# Oscar_MainBoard_LCD.net
KiCad netlist of a schematic drawn in Altium Designer
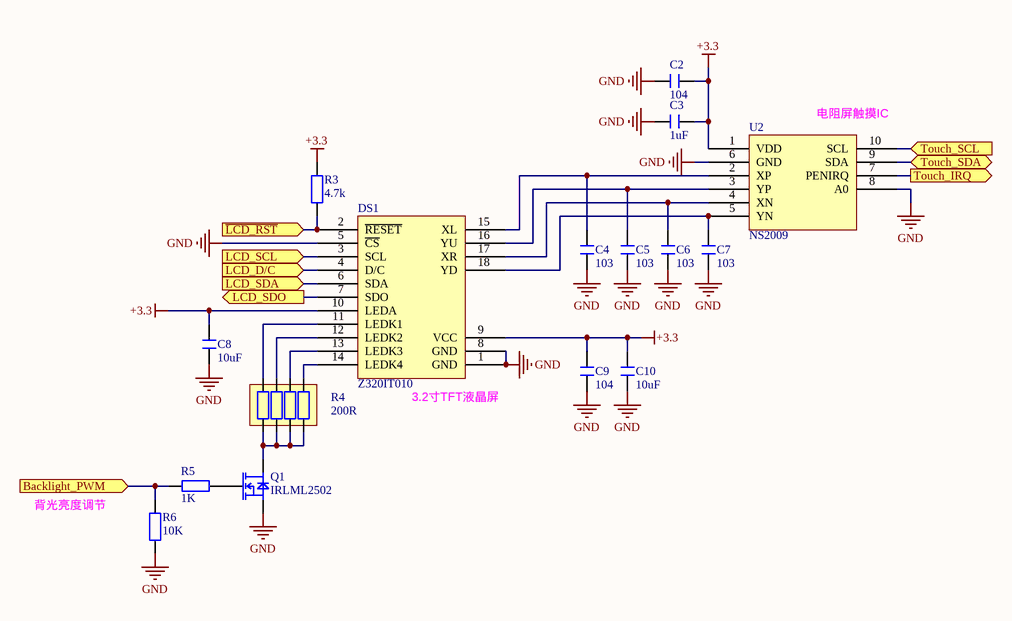
[diagram p0: Oscar_MainBoard_LCD.SchDoc]

(export (version "E")
  (design (tool "Eeschema 10.0.6"))
  (components
    (comp (ref "C2")
      (value "104")
      (footprint "C 0402_L")
      (description "贴片电容")
      (libsource (lib "0.1 - 电阻-电容-电感") (part "C"))
    )
    (comp (ref "C3")
      (value "1uF")
      (footprint "C 0402_L")
      (description "贴片电容")
      (libsource (lib "0.1 - 电阻-电容-电感") (part "C"))
    )
    (comp (ref "C4")
      (value "103")
      (footprint "C 0402_L")
      (description "贴片电容")
      (libsource (lib "0.1 - 电阻-电容-电感") (part "C"))
    )
    (comp (ref "C5")
      (value "103")
      (footprint "C 0402_L")
      (description "贴片电容")
      (libsource (lib "0.1 - 电阻-电容-电感") (part "C"))
    )
    (comp (ref "C6")
      (value "103")
      (footprint "C 0402_L")
      (description "贴片电容")
      (libsource (lib "0.1 - 电阻-电容-电感") (part "C"))
    )
    (comp (ref "C7")
      (value "103")
      (footprint "C 0402_L")
      (description "贴片电容")
      (libsource (lib "0.1 - 电阻-电容-电感") (part "C"))
    )
    (comp (ref "C8")
      (value "10uF")
      (footprint "C 0603_L")
      (description "贴片电容")
      (libsource (lib "0.1 - 电阻-电容-电感") (part "C"))
    )
    (comp (ref "C9")
      (value "104")
      (footprint "C 0402_L")
      (description "贴片电容")
      (libsource (lib "0.1 - 电阻-电容-电感") (part "C"))
    )
    (comp (ref "C10")
      (value "10uF")
      (footprint "C 0603_L")
      (description "贴片电容")
      (libsource (lib "0.1 - 电阻-电容-电感") (part "C"))
    )
    (comp (ref "DS1")
      (value "Z320IT010")
      (footprint "Z320IT010")
      (description "3.2 inch TFT_LCD SPI")
      (libsource (lib "显示器件") (part "Z320IT010"))
    )
    (comp (ref "Q1")
      (value "IRLML2502")
      (footprint "SOT23-3n")
      (description "MOSFET N沟道 20V/4.2A")
      (libsource (lib "0.4 - 三极管-场效应管-可控硅") (part "IRLML2502"))
    )
    (comp (ref "R3")
      (value "4.7k")
      (footprint "R 0402_L")
      (description "贴片电阻")
      (libsource (lib "0.1 - 电阻-电容-电感") (part "R"))
    )
    (comp (ref "R4")
      (value "200R")
      (footprint "RCA-8P4R-0402")
      (description "贴片排阻")
      (libsource (lib "0.1 - 电阻-电容-电感") (part "R-8P4R"))
    )
    (comp (ref "R5")
      (value "1K")
      (footprint "R 0402_L")
      (description "贴片电阻")
      (libsource (lib "0.1 - 电阻-电容-电感") (part "R"))
    )
    (comp (ref "R6")
      (value "10K")
      (footprint "R 0402_L")
      (description "贴片电阻")
      (libsource (lib "0.1 - 电阻-电容-电感") (part "R"))
    )
    (comp (ref "U2")
      (value "NS2009")
      (footprint "MSOP10_N")
      (description "I2C接口的4线制电阻式触摸屏控制电路")
      (libsource (lib "显示器件") (part "NS2009"))
    )
  )
  (nets
    (net (code "1") (name "+3.3") (class "Default")
      (node (ref "C10") (pin "1") (pinfunction "1_1") (pintype "passive"))
      (node (ref "C2") (pin "1") (pinfunction "1_1") (pintype "passive"))
      (node (ref "C3") (pin "1") (pinfunction "1_1") (pintype "passive"))
      (node (ref "C8") (pin "1") (pinfunction "1_1") (pintype "passive"))
      (node (ref "C9") (pin "1") (pinfunction "1_1") (pintype "passive"))
      (node (ref "DS1") (pin "10") (pinfunction "LEDA_10") (pintype "passive"))
      (node (ref "DS1") (pin "9") (pinfunction "VCC_9") (pintype "passive"))
      (node (ref "R3") (pin "2") (pinfunction "2_2") (pintype "passive"))
      (node (ref "U2") (pin "1") (pinfunction "VDD_1") (pintype "passive"))
    )
    (net (code "2") (name "/Backlight_PWM") (class "Default")
      (node (ref "R5") (pin "1") (pinfunction "1_1") (pintype "passive"))
      (node (ref "R6") (pin "2") (pinfunction "2_2") (pintype "passive"))
    )
    (net (code "3") (name "/LCD_D{slash}C") (class "Default")
      (node (ref "DS1") (pin "4") (pinfunction "D/C_4") (pintype "passive"))
    )
    (net (code "4") (name "/LCD_SCL") (class "Default")
      (node (ref "DS1") (pin "3") (pinfunction "SCL_3") (pintype "passive"))
    )
    (net (code "5") (name "/LCD_SDA") (class "Default")
      (node (ref "DS1") (pin "6") (pinfunction "SDA_6") (pintype "passive"))
    )
    (net (code "6") (name "/LCD_SDO") (class "Default")
      (node (ref "DS1") (pin "7") (pinfunction "SDO_7") (pintype "passive"))
    )
    (net (code "7") (name "/Touch_IRQ") (class "Default")
      (node (ref "U2") (pin "7") (pinfunction "PENIRQ_7") (pintype "passive"))
    )
    (net (code "8") (name "/Touch_SCL") (class "Default")
      (node (ref "U2") (pin "10") (pinfunction "SCL_10") (pintype "passive"))
    )
    (net (code "9") (name "/Touch_SDA") (class "Default")
      (node (ref "U2") (pin "9") (pinfunction "SDA_9") (pintype "passive"))
    )
    (net (code "10") (name "/~{LCD_RST}") (class "Default")
      (node (ref "DS1") (pin "2") (pinfunction "~{RESET}_2") (pintype "passive"))
      (node (ref "R3") (pin "1") (pinfunction "1_1") (pintype "passive"))
    )
    (net (code "11") (name "GND") (class "Default")
      (node (ref "C10") (pin "2") (pinfunction "2_2") (pintype "passive"))
      (node (ref "C2") (pin "2") (pinfunction "2_2") (pintype "passive"))
      (node (ref "C3") (pin "2") (pinfunction "2_2") (pintype "passive"))
      (node (ref "C4") (pin "2") (pinfunction "2_2") (pintype "passive"))
      (node (ref "C5") (pin "2") (pinfunction "2_2") (pintype "passive"))
      (node (ref "C6") (pin "2") (pinfunction "2_2") (pintype "passive"))
      (node (ref "C7") (pin "2") (pinfunction "2_2") (pintype "passive"))
      (node (ref "C8") (pin "2") (pinfunction "2_2") (pintype "passive"))
      (node (ref "C9") (pin "2") (pinfunction "2_2") (pintype "passive"))
      (node (ref "DS1") (pin "1") (pinfunction "GND_1") (pintype "passive"))
      (node (ref "DS1") (pin "5") (pinfunction "~{CS}_5") (pintype "passive"))
      (node (ref "DS1") (pin "8") (pinfunction "GND_8") (pintype "passive"))
      (node (ref "Q1") (pin "2") (pinfunction "S_2") (pintype "passive"))
      (node (ref "R6") (pin "1") (pinfunction "1_1") (pintype "passive"))
      (node (ref "U2") (pin "6") (pinfunction "GND_6") (pintype "passive"))
      (node (ref "U2") (pin "8") (pinfunction "A0_8") (pintype "passive"))
    )
    (net (code "12") (name "Net-(DS1-LEDK1)") (class "Default")
      (node (ref "DS1") (pin "11") (pinfunction "LEDK1_11") (pintype "passive"))
      (node (ref "R4") (pin "8") (pinfunction "8_8") (pintype "passive"))
    )
    (net (code "13") (name "Net-(DS1-LEDK2)") (class "Default")
      (node (ref "DS1") (pin "12") (pinfunction "LEDK2_12") (pintype "passive"))
      (node (ref "R4") (pin "7") (pinfunction "7_7") (pintype "passive"))
    )
    (net (code "14") (name "Net-(DS1-LEDK3)") (class "Default")
      (node (ref "DS1") (pin "13") (pinfunction "LEDK3_13") (pintype "passive"))
      (node (ref "R4") (pin "6") (pinfunction "6_6") (pintype "passive"))
    )
    (net (code "15") (name "Net-(DS1-LEDK4)") (class "Default")
      (node (ref "DS1") (pin "14") (pinfunction "LEDK4_14") (pintype "passive"))
      (node (ref "R4") (pin "5") (pinfunction "5_5") (pintype "passive"))
    )
    (net (code "16") (name "Net-(DS1-XL)") (class "Default")
      (node (ref "C4") (pin "1") (pinfunction "1_1") (pintype "passive"))
      (node (ref "DS1") (pin "15") (pinfunction "XL_15") (pintype "passive"))
      (node (ref "U2") (pin "2") (pinfunction "XP_2") (pintype "passive"))
    )
    (net (code "17") (name "Net-(DS1-XR)") (class "Default")
      (node (ref "C6") (pin "1") (pinfunction "1_1") (pintype "passive"))
      (node (ref "DS1") (pin "17") (pinfunction "XR_17") (pintype "passive"))
      (node (ref "U2") (pin "4") (pinfunction "XN_4") (pintype "passive"))
    )
    (net (code "18") (name "Net-(DS1-YD)") (class "Default")
      (node (ref "C7") (pin "1") (pinfunction "1_1") (pintype "passive"))
      (node (ref "DS1") (pin "18") (pinfunction "YD_18") (pintype "passive"))
      (node (ref "U2") (pin "5") (pinfunction "YN_5") (pintype "passive"))
    )
    (net (code "19") (name "Net-(DS1-YU)") (class "Default")
      (node (ref "C5") (pin "1") (pinfunction "1_1") (pintype "passive"))
      (node (ref "DS1") (pin "16") (pinfunction "YU_16") (pintype "passive"))
      (node (ref "U2") (pin "3") (pinfunction "YP_3") (pintype "passive"))
    )
    (net (code "20") (name "Net-(Q1-D)") (class "Default")
      (node (ref "Q1") (pin "3") (pinfunction "D_3") (pintype "passive"))
      (node (ref "R4") (pin "1") (pinfunction "1_1") (pintype "passive"))
      (node (ref "R4") (pin "2") (pinfunction "2_2") (pintype "passive"))
      (node (ref "R4") (pin "3") (pinfunction "3_3") (pintype "passive"))
      (node (ref "R4") (pin "4") (pinfunction "4_4") (pintype "passive"))
    )
    (net (code "21") (name "Net-(Q1-G)") (class "Default")
      (node (ref "Q1") (pin "1") (pinfunction "G_1") (pintype "passive"))
      (node (ref "R5") (pin "2") (pinfunction "2_2") (pintype "passive"))
    )
  )
)
